# STM32_BOARD.net
KiCad netlist of a schematic drawn in Altium Designer
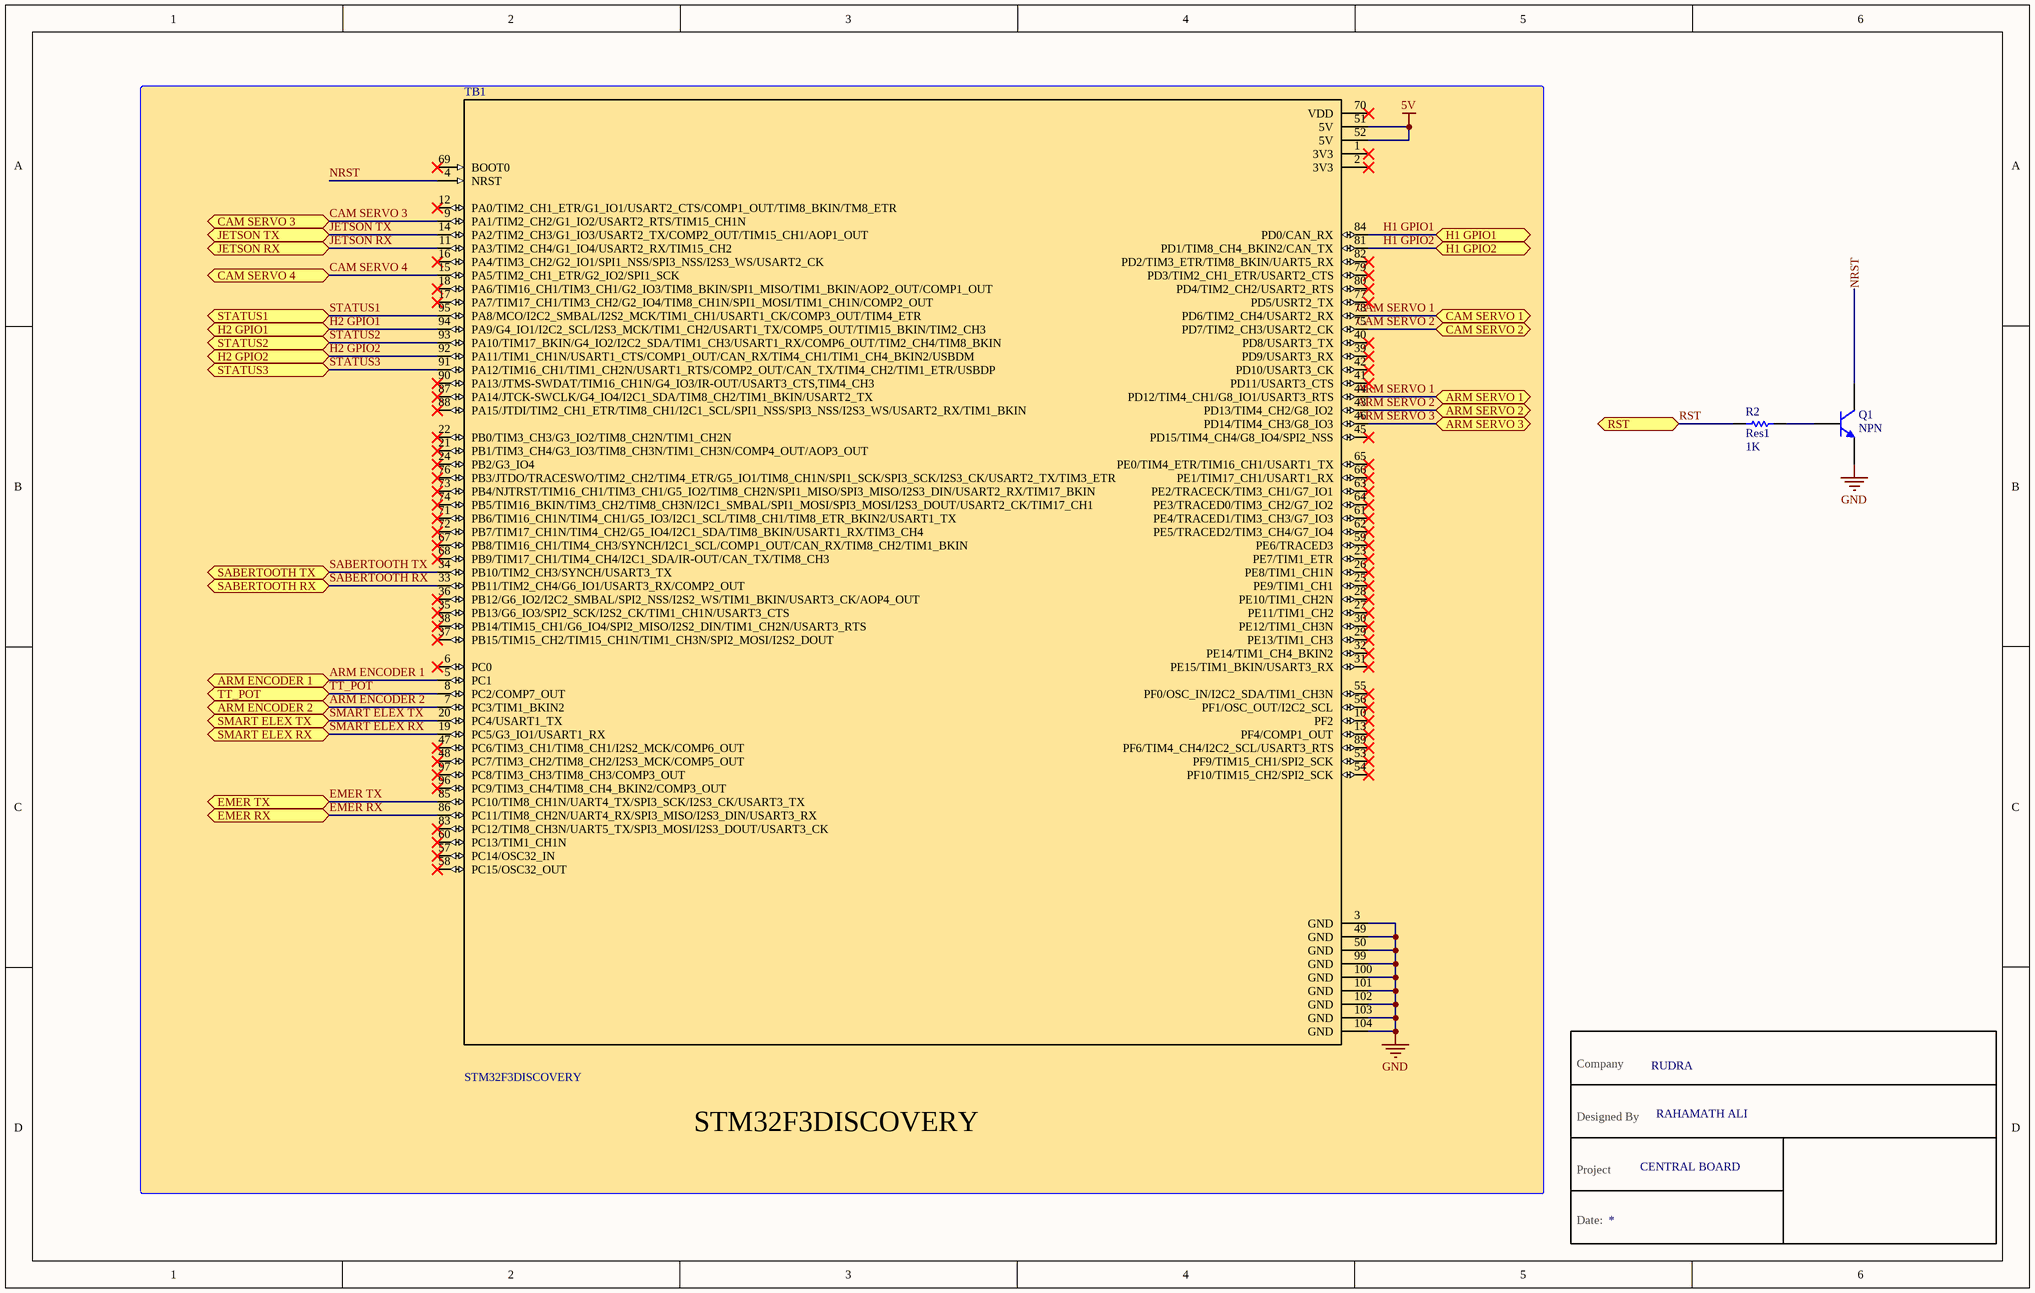
[diagram p0: STM32 BOARD.SchDoc]

(export (version "E")
  (design (tool "Eeschema 10.0.6"))
  (components
    (comp (ref "1")
      (value "Schematic Table")
      (fields
        (field (name "PROJECT") "CENTRAL BOARD")
        (field (name "DESIGNED BY") "RAHAMATH ALI")
        (field (name "COMPANY") "RUDRA")
      )
      (libsource (lib "schmatic") (part "Schematic Table"))
    )
    (comp (ref "Q1")
      (value "NPN")
      (footprint "TO-226-AA")
      (description "NPN Bipolar Transistor")
      (fields (field (name "PUBLISHER") "Altium Limited"))
      (libsource (lib "Miscellaneous Devices") (part "NPN"))
    )
    (comp (ref "R2")
      (value "Res1")
      (footprint "AXIAL-0.3")
      (description "Resistor")
      (fields (field (name "ALTIUM_VALUE") "1K") (field (name "PUBLISHER") "Altium Limited"))
      (libsource (lib "Miscellaneous Devices") (part "Res1"))
    )
    (comp (ref "TB1")
      (value "STM32F3DISCOVERY")
      (footprint "SHIELD_STM32F3DISCOVERY")
      (description "STM32F303VCT6 Discovery STM32F3 ARMÂ® CortexÂ®-M4 MCU 32-Bit Embedded Evaluation Board")
      (fields (field (name "MF") "STMicroelectronics"))
      (libsource (lib "CENTRAL BOARD LIBARAY") (part "STM32F3DISCOVERY"))
    )
  )
  (nets
    (net (code "1") (name "/ARM ENCODER 1") (class "Default")
      (node (ref "TB1") (pin "5") (pinfunction "PC1_5") (pintype "bidirectional"))
    )
    (net (code "2") (name "/ARM ENCODER 2") (class "Default")
      (node (ref "TB1") (pin "7") (pinfunction "PC3/TIM1_BKIN2_7") (pintype "bidirectional"))
    )
    (net (code "3") (name "/ARM SERVO 1") (class "Default")
      (node (ref "TB1") (pin "44") (pinfunction "PD12/TIM4_CH1/G8_IO1/USART3_RTS_44") (pintype "bidirectional"))
    )
    (net (code "4") (name "/ARM SERVO 2") (class "Default")
      (node (ref "TB1") (pin "43") (pinfunction "PD13/TIM4_CH2/G8_IO2_43") (pintype "bidirectional"))
    )
    (net (code "5") (name "/ARM SERVO 3") (class "Default")
      (node (ref "TB1") (pin "46") (pinfunction "PD14/TIM4_CH3/G8_IO3_46") (pintype "bidirectional"))
    )
    (net (code "6") (name "/CAM SERVO 1") (class "Default")
      (node (ref "TB1") (pin "78") (pinfunction "PD6/TIM2_CH4/USART2_RX_78") (pintype "bidirectional"))
    )
    (net (code "7") (name "/CAM SERVO 2") (class "Default")
      (node (ref "TB1") (pin "75") (pinfunction "PD7/TIM2_CH3/USART2_CK_75") (pintype "bidirectional"))
    )
    (net (code "8") (name "/CAM SERVO 3") (class "Default")
      (node (ref "TB1") (pin "9") (pinfunction "PA1/TIM2_CH2/G1_IO2/USART2_RTS/TIM15_CH1N_9") (pintype "bidirectional"))
    )
    (net (code "9") (name "/CAM SERVO 4") (class "Default")
      (node (ref "TB1") (pin "15") (pinfunction "PA5/TIM2_CH1_ETR/G2_IO2/SPI1_SCK_15") (pintype "bidirectional"))
    )
    (net (code "10") (name "/EMER RX") (class "Default")
      (node (ref "TB1") (pin "86") (pinfunction "PC11/TIM8_CH2N/UART4_RX/SPI3_MISO/I2S3_DIN/USART3_RX_86") (pintype "bidirectional"))
    )
    (net (code "11") (name "/EMER TX") (class "Default")
      (node (ref "TB1") (pin "85") (pinfunction "PC10/TIM8_CH1N/UART4_TX/SPI3_SCK/I2S3_CK/USART3_TX_85") (pintype "bidirectional"))
    )
    (net (code "12") (name "/H1 GPIO1") (class "Default")
      (node (ref "TB1") (pin "84") (pinfunction "PD0/CAN_RX_84") (pintype "bidirectional"))
    )
    (net (code "13") (name "/H1 GPIO2") (class "Default")
      (node (ref "TB1") (pin "81") (pinfunction "PD1/TIM8_CH4_BKIN2/CAN_TX_81") (pintype "bidirectional"))
    )
    (net (code "14") (name "/H2 GPIO1") (class "Default")
      (node (ref "TB1") (pin "94") (pinfunction "PA9/G4_IO1/I2C2_SCL/I2S3_MCK/TIM1_CH2/USART1_TX/COMP5_OUT/TIM15_BKIN/TIM2_CH3_94") (pintype "bidirectional"))
    )
    (net (code "15") (name "/H2 GPIO2") (class "Default")
      (node (ref "TB1") (pin "92") (pinfunction "PA11/TIM1_CH1N/USART1_CTS/COMP1_OUT/CAN_RX/TIM4_CH1/TIM1_CH4_BKIN2/USBDM_92") (pintype "bidirectional"))
    )
    (net (code "16") (name "/JETSON RX") (class "Default")
      (node (ref "TB1") (pin "11") (pinfunction "PA3/TIM2_CH4/G1_IO4/USART2_RX/TIM15_CH2_11") (pintype "bidirectional"))
    )
    (net (code "17") (name "/JETSON TX") (class "Default")
      (node (ref "TB1") (pin "14") (pinfunction "PA2/TIM2_CH3/G1_IO3/USART2_TX/COMP2_OUT/TIM15_CH1/AOP1_OUT_14") (pintype "bidirectional"))
    )
    (net (code "18") (name "/NRST") (class "Default")
      (node (ref "Q1") (pin "1") (pinfunction "C_1") (pintype "passive"))
      (node (ref "TB1") (pin "4") (pinfunction "NRST_4") (pintype "input"))
    )
    (net (code "19") (name "/RST") (class "Default")
      (node (ref "R2") (pin "1") (pinfunction "1_1") (pintype "passive"))
    )
    (net (code "20") (name "/SABERTOOTH RX") (class "Default")
      (node (ref "TB1") (pin "33") (pinfunction "PB11/TIM2_CH4/G6_IO1/USART3_RX/COMP2_OUT_33") (pintype "bidirectional"))
    )
    (net (code "21") (name "/SABERTOOTH TX") (class "Default")
      (node (ref "TB1") (pin "34") (pinfunction "PB10/TIM2_CH3/SYNCH/USART3_TX_34") (pintype "bidirectional"))
    )
    (net (code "22") (name "/SMART ELEX RX") (class "Default")
      (node (ref "TB1") (pin "19") (pinfunction "PC5/G3_IO1/USART1_RX_19") (pintype "bidirectional"))
    )
    (net (code "23") (name "/SMART ELEX TX") (class "Default")
      (node (ref "TB1") (pin "20") (pinfunction "PC4/USART1_TX_20") (pintype "bidirectional"))
    )
    (net (code "24") (name "/STATUS1") (class "Default")
      (node (ref "TB1") (pin "95") (pinfunction "PA8/MCO/I2C2_SMBAL/I2S2_MCK/TIM1_CH1/USART1_CK/COMP3_OUT/TIM4_ETR_95") (pintype "bidirectional"))
    )
    (net (code "25") (name "/STATUS2") (class "Default")
      (node (ref "TB1") (pin "93") (pinfunction "PA10/TIM17_BKIN/G4_IO2/I2C2_SDA/TIM1_CH3/USART1_RX/COMP6_OUT/TIM2_CH4/TIM8_BKIN_93") (pintype "bidirectional"))
    )
    (net (code "26") (name "/STATUS3") (class "Default")
      (node (ref "TB1") (pin "91") (pinfunction "PA12/TIM16_CH1/TIM1_CH2N/USART1_RTS/COMP2_OUT/CAN_TX/TIM4_CH2/TIM1_ETR/USBDP_91") (pintype "bidirectional"))
    )
    (net (code "27") (name "/TT_POT") (class "Default")
      (node (ref "TB1") (pin "8") (pinfunction "PC2/COMP7_OUT_8") (pintype "bidirectional"))
    )
    (net (code "28") (name "5V") (class "Default")
      (node (ref "TB1") (pin "51") (pinfunction "5V_51") (pintype "power_in"))
      (node (ref "TB1") (pin "52") (pinfunction "5V_52") (pintype "power_in"))
    )
    (net (code "29") (name "GND") (class "Default")
      (node (ref "Q1") (pin "3") (pinfunction "E_3") (pintype "passive"))
      (node (ref "TB1") (pin "100") (pinfunction "GND_100") (pintype "power_in"))
      (node (ref "TB1") (pin "101") (pinfunction "GND_101") (pintype "power_in"))
      (node (ref "TB1") (pin "102") (pinfunction "GND_102") (pintype "power_in"))
      (node (ref "TB1") (pin "103") (pinfunction "GND_103") (pintype "power_in"))
      (node (ref "TB1") (pin "104") (pinfunction "GND_104") (pintype "power_in"))
      (node (ref "TB1") (pin "3") (pinfunction "GND_3") (pintype "power_in"))
      (node (ref "TB1") (pin "49") (pinfunction "GND_49") (pintype "power_in"))
      (node (ref "TB1") (pin "50") (pinfunction "GND_50") (pintype "power_in"))
      (node (ref "TB1") (pin "99") (pinfunction "GND_99") (pintype "power_in"))
    )
    (net (code "30") (name "Net-(Q1-B)") (class "Default")
      (node (ref "Q1") (pin "2") (pinfunction "B_2") (pintype "passive"))
      (node (ref "R2") (pin "2") (pinfunction "2_2") (pintype "passive"))
    )
    (net (code "31") (name "unconnected-(TB1-3V3-Pad1)") (class "Default")
      (node (ref "TB1") (pin "1") (pinfunction "3V3_1") (pintype "power_in+no_connect"))
    )
    (net (code "32") (name "unconnected-(TB1-3V3-Pad2)") (class "Default")
      (node (ref "TB1") (pin "2") (pinfunction "3V3_2") (pintype "power_in+no_connect"))
    )
    (net (code "33") (name "unconnected-(TB1-BOOT0-Pad69)") (class "Default")
      (node (ref "TB1") (pin "69") (pinfunction "BOOT0_69") (pintype "input+no_connect"))
    )
    (net (code "34") (name "unconnected-(TB1-PA0{slash}TIM2_CH1_ETR{slash}G1_IO1{slash}USART2_CTS{slash}COMP1_OUT{slash}TIM8_BKIN{slash}TM8_ETR-Pad12)") (class "Default")
      (node (ref "TB1") (pin "12") (pinfunction "PA0/TIM2_CH1_ETR/G1_IO1/USART2_CTS/COMP1_OUT/TIM8_BKIN/TM8_ETR_12") (pintype "bidirectional+no_connect"))
    )
    (net (code "35") (name "unconnected-(TB1-PA4{slash}TIM3_CH2{slash}G2_IO1{slash}SPI1_NSS{slash}SPI3_NSS{slash}I2S3_WS{slash}USART2_CK-Pad16)") (class "Default")
      (node (ref "TB1") (pin "16") (pinfunction "PA4/TIM3_CH2/G2_IO1/SPI1_NSS/SPI3_NSS/I2S3_WS/USART2_CK_16") (pintype "bidirectional+no_connect"))
    )
    (net (code "36") (name "unconnected-(TB1-PA6{slash}TIM16_CH1{slash}TIM3_CH1{slash}G2_IO3{slash}TIM8_BKIN{slash}SPI1_MISO{slash}TIM1_BKIN{slash}AOP2_OUT{slash}COMP1_OUT-Pad18)") (class "Default")
      (node (ref "TB1") (pin "18") (pinfunction "PA6/TIM16_CH1/TIM3_CH1/G2_IO3/TIM8_BKIN/SPI1_MISO/TIM1_BKIN/AOP2_OUT/COMP1_OUT_18") (pintype "bidirectional+no_connect"))
    )
    (net (code "37") (name "unconnected-(TB1-PA7{slash}TIM17_CH1{slash}TIM3_CH2{slash}G2_IO4{slash}TIM8_CH1N{slash}SPI1_MOSI{slash}TIM1_CH1N{slash}COMP2_OUT-Pad17)") (class "Default")
      (node (ref "TB1") (pin "17") (pinfunction "PA7/TIM17_CH1/TIM3_CH2/G2_IO4/TIM8_CH1N/SPI1_MOSI/TIM1_CH1N/COMP2_OUT_17") (pintype "bidirectional+no_connect"))
    )
    (net (code "38") (name "unconnected-(TB1-PA13{slash}JTMS-SWDAT{slash}TIM16_CH1N{slash}G4_IO3{slash}IR-OUT{slash}USART3_CTS,TIM4_CH3-Pad90)") (class "Default")
      (node (ref "TB1") (pin "90") (pinfunction "PA13/JTMS-SWDAT/TIM16_CH1N/G4_IO3/IR-OUT/USART3_CTS,TIM4_CH3_90") (pintype "bidirectional+no_connect"))
    )
    (net (code "39") (name "unconnected-(TB1-PA14{slash}JTCK-SWCLK{slash}G4_IO4{slash}I2C1_SDA{slash}TIM8_CH2{slash}TIM1_BKIN{slash}USART2_TX-Pad87)") (class "Default")
      (node (ref "TB1") (pin "87") (pinfunction "PA14/JTCK-SWCLK/G4_IO4/I2C1_SDA/TIM8_CH2/TIM1_BKIN/USART2_TX_87") (pintype "bidirectional+no_connect"))
    )
    (net (code "40") (name "unconnected-(TB1-PA15{slash}JTDI{slash}TIM2_CH1_ETR{slash}TIM8_CH1{slash}I2C1_SCL{slash}SPI1_NSS{slash}SPI3_NSS{slash}I2S3_WS{slash}USART2_RX{slash}TIM1_BKIN-Pad88)") (class "Default")
      (node (ref "TB1") (pin "88") (pinfunction "PA15/JTDI/TIM2_CH1_ETR/TIM8_CH1/I2C1_SCL/SPI1_NSS/SPI3_NSS/I2S3_WS/USART2_RX/TIM1_BKIN_88") (pintype "bidirectional+no_connect"))
    )
    (net (code "41") (name "unconnected-(TB1-PB0{slash}TIM3_CH3{slash}G3_IO2{slash}TIM8_CH2N{slash}TIM1_CH2N-Pad22)") (class "Default")
      (node (ref "TB1") (pin "22") (pinfunction "PB0/TIM3_CH3/G3_IO2/TIM8_CH2N/TIM1_CH2N_22") (pintype "bidirectional+no_connect"))
    )
    (net (code "42") (name "unconnected-(TB1-PB1{slash}TIM3_CH4{slash}G3_IO3{slash}TIM8_CH3N{slash}TIM1_CH3N{slash}COMP4_OUT{slash}AOP3_OUT-Pad21)") (class "Default")
      (node (ref "TB1") (pin "21") (pinfunction "PB1/TIM3_CH4/G3_IO3/TIM8_CH3N/TIM1_CH3N/COMP4_OUT/AOP3_OUT_21") (pintype "bidirectional+no_connect"))
    )
    (net (code "43") (name "unconnected-(TB1-PB2{slash}G3_IO4-Pad24)") (class "Default")
      (node (ref "TB1") (pin "24") (pinfunction "PB2/G3_IO4_24") (pintype "bidirectional+no_connect"))
    )
    (net (code "44") (name "unconnected-(TB1-PB3{slash}JTDO{slash}TRACESWO{slash}TIM2_CH2{slash}TIM4_ETR{slash}G5_IO1{slash}TIM8_CH1N{slash}SPI1_SCK{slash}SPI3_SCK{slash}I2S3_CK{slash}USART2_TX{slash}TIM3_ETR-Pad76)") (class "Default")
      (node (ref "TB1") (pin "76") (pinfunction "PB3/JTDO/TRACESWO/TIM2_CH2/TIM4_ETR/G5_IO1/TIM8_CH1N/SPI1_SCK/SPI3_SCK/I2S3_CK/USART2_TX/TIM3_ETR_76") (pintype "bidirectional+no_connect"))
    )
    (net (code "45") (name "unconnected-(TB1-PB4{slash}NJTRST{slash}TIM16_CH1{slash}TIM3_CH1{slash}G5_IO2{slash}TIM8_CH2N{slash}SPI1_MISO{slash}SPI3_MISO{slash}I2S3_DIN{slash}USART2_RX{slash}TIM17_BKIN-Pad73)") (class "Default")
      (node (ref "TB1") (pin "73") (pinfunction "PB4/NJTRST/TIM16_CH1/TIM3_CH1/G5_IO2/TIM8_CH2N/SPI1_MISO/SPI3_MISO/I2S3_DIN/USART2_RX/TIM17_BKIN_73") (pintype "bidirectional+no_connect"))
    )
    (net (code "46") (name "unconnected-(TB1-PB5{slash}TIM16_BKIN{slash}TIM3_CH2{slash}TIM8_CH3N{slash}I2C1_SMBAL{slash}SPI1_MOSI{slash}SPI3_MOSI{slash}I2S3_DOUT{slash}USART2_CK{slash}TIM17_CH1-Pad74)") (class "Default")
      (node (ref "TB1") (pin "74") (pinfunction "PB5/TIM16_BKIN/TIM3_CH2/TIM8_CH3N/I2C1_SMBAL/SPI1_MOSI/SPI3_MOSI/I2S3_DOUT/USART2_CK/TIM17_CH1_74") (pintype "bidirectional+no_connect"))
    )
    (net (code "47") (name "unconnected-(TB1-PB6{slash}TIM16_CH1N{slash}TIM4_CH1{slash}G5_IO3{slash}I2C1_SCL{slash}TIM8_CH1{slash}TIM8_ETR_BKIN2{slash}USART1_TX-Pad71)") (class "Default")
      (node (ref "TB1") (pin "71") (pinfunction "PB6/TIM16_CH1N/TIM4_CH1/G5_IO3/I2C1_SCL/TIM8_CH1/TIM8_ETR_BKIN2/USART1_TX_71") (pintype "bidirectional+no_connect"))
    )
    (net (code "48") (name "unconnected-(TB1-PB7{slash}TIM17_CH1N{slash}TIM4_CH2{slash}G5_IO4{slash}I2C1_SDA{slash}TIM8_BKIN{slash}USART1_RX{slash}TIM3_CH4-Pad72)") (class "Default")
      (node (ref "TB1") (pin "72") (pinfunction "PB7/TIM17_CH1N/TIM4_CH2/G5_IO4/I2C1_SDA/TIM8_BKIN/USART1_RX/TIM3_CH4_72") (pintype "bidirectional+no_connect"))
    )
    (net (code "49") (name "unconnected-(TB1-PB8{slash}TIM16_CH1{slash}TIM4_CH3{slash}SYNCH{slash}I2C1_SCL{slash}COMP1_OUT{slash}CAN_RX{slash}TIM8_CH2{slash}TIM1_BKIN-Pad67)") (class "Default")
      (node (ref "TB1") (pin "67") (pinfunction "PB8/TIM16_CH1/TIM4_CH3/SYNCH/I2C1_SCL/COMP1_OUT/CAN_RX/TIM8_CH2/TIM1_BKIN_67") (pintype "bidirectional+no_connect"))
    )
    (net (code "50") (name "unconnected-(TB1-PB9{slash}TIM17_CH1{slash}TIM4_CH4{slash}I2C1_SDA{slash}IR-OUT{slash}CAN_TX{slash}TIM8_CH3-Pad68)") (class "Default")
      (node (ref "TB1") (pin "68") (pinfunction "PB9/TIM17_CH1/TIM4_CH4/I2C1_SDA/IR-OUT/CAN_TX/TIM8_CH3_68") (pintype "bidirectional+no_connect"))
    )
    (net (code "51") (name "unconnected-(TB1-PB12{slash}G6_IO2{slash}I2C2_SMBAL{slash}SPI2_NSS{slash}I2S2_WS{slash}TIM1_BKIN{slash}USART3_CK{slash}AOP4_OUT-Pad36)") (class "Default")
      (node (ref "TB1") (pin "36") (pinfunction "PB12/G6_IO2/I2C2_SMBAL/SPI2_NSS/I2S2_WS/TIM1_BKIN/USART3_CK/AOP4_OUT_36") (pintype "bidirectional+no_connect"))
    )
    (net (code "52") (name "unconnected-(TB1-PB13{slash}G6_IO3{slash}SPI2_SCK{slash}I2S2_CK{slash}TIM1_CH1N{slash}USART3_CTS-Pad35)") (class "Default")
      (node (ref "TB1") (pin "35") (pinfunction "PB13/G6_IO3/SPI2_SCK/I2S2_CK/TIM1_CH1N/USART3_CTS_35") (pintype "bidirectional+no_connect"))
    )
    (net (code "53") (name "unconnected-(TB1-PB14{slash}TIM15_CH1{slash}G6_IO4{slash}SPI2_MISO{slash}I2S2_DIN{slash}TIM1_CH2N{slash}USART3_RTS-Pad38)") (class "Default")
      (node (ref "TB1") (pin "38") (pinfunction "PB14/TIM15_CH1/G6_IO4/SPI2_MISO/I2S2_DIN/TIM1_CH2N/USART3_RTS_38") (pintype "bidirectional+no_connect"))
    )
    (net (code "54") (name "unconnected-(TB1-PB15{slash}TIM15_CH2{slash}TIM15_CH1N{slash}TIM1_CH3N{slash}SPI2_MOSI{slash}I2S2_DOUT-Pad37)") (class "Default")
      (node (ref "TB1") (pin "37") (pinfunction "PB15/TIM15_CH2/TIM15_CH1N/TIM1_CH3N/SPI2_MOSI/I2S2_DOUT_37") (pintype "bidirectional+no_connect"))
    )
    (net (code "55") (name "unconnected-(TB1-PC0-Pad6)") (class "Default")
      (node (ref "TB1") (pin "6") (pinfunction "PC0_6") (pintype "bidirectional+no_connect"))
    )
    (net (code "56") (name "unconnected-(TB1-PC6{slash}TIM3_CH1{slash}TIM8_CH1{slash}I2S2_MCK{slash}COMP6_OUT-Pad47)") (class "Default")
      (node (ref "TB1") (pin "47") (pinfunction "PC6/TIM3_CH1/TIM8_CH1/I2S2_MCK/COMP6_OUT_47") (pintype "bidirectional+no_connect"))
    )
    (net (code "57") (name "unconnected-(TB1-PC7{slash}TIM3_CH2{slash}TIM8_CH2{slash}I2S3_MCK{slash}COMP5_OUT-Pad48)") (class "Default")
      (node (ref "TB1") (pin "48") (pinfunction "PC7/TIM3_CH2/TIM8_CH2/I2S3_MCK/COMP5_OUT_48") (pintype "bidirectional+no_connect"))
    )
    (net (code "58") (name "unconnected-(TB1-PC8{slash}TIM3_CH3{slash}TIM8_CH3{slash}COMP3_OUT-Pad97)") (class "Default")
      (node (ref "TB1") (pin "97") (pinfunction "PC8/TIM3_CH3/TIM8_CH3/COMP3_OUT_97") (pintype "bidirectional+no_connect"))
    )
    (net (code "59") (name "unconnected-(TB1-PC9{slash}TIM3_CH4{slash}TIM8_CH4_BKIN2{slash}COMP3_OUT-Pad96)") (class "Default")
      (node (ref "TB1") (pin "96") (pinfunction "PC9/TIM3_CH4/TIM8_CH4_BKIN2/COMP3_OUT_96") (pintype "bidirectional+no_connect"))
    )
    (net (code "60") (name "unconnected-(TB1-PC12{slash}TIM8_CH3N{slash}UART5_TX{slash}SPI3_MOSI{slash}I2S3_DOUT{slash}USART3_CK-Pad83)") (class "Default")
      (node (ref "TB1") (pin "83") (pinfunction "PC12/TIM8_CH3N/UART5_TX/SPI3_MOSI/I2S3_DOUT/USART3_CK_83") (pintype "bidirectional+no_connect"))
    )
    (net (code "61") (name "unconnected-(TB1-PC13{slash}TIM1_CH1N-Pad60)") (class "Default")
      (node (ref "TB1") (pin "60") (pinfunction "PC13/TIM1_CH1N_60") (pintype "bidirectional+no_connect"))
    )
    (net (code "62") (name "unconnected-(TB1-PC14{slash}OSC32_IN-Pad57)") (class "Default")
      (node (ref "TB1") (pin "57") (pinfunction "PC14/OSC32_IN_57") (pintype "bidirectional+no_connect"))
    )
    (net (code "63") (name "unconnected-(TB1-PC15{slash}OSC32_OUT-Pad58)") (class "Default")
      (node (ref "TB1") (pin "58") (pinfunction "PC15/OSC32_OUT_58") (pintype "bidirectional+no_connect"))
    )
    (net (code "64") (name "unconnected-(TB1-PD2{slash}TIM3_ETR{slash}TIM8_BKIN{slash}UART5_RX-Pad82)") (class "Default")
      (node (ref "TB1") (pin "82") (pinfunction "PD2/TIM3_ETR/TIM8_BKIN/UART5_RX_82") (pintype "bidirectional+no_connect"))
    )
    (net (code "65") (name "unconnected-(TB1-PD3{slash}TIM2_CH1_ETR{slash}USART2_CTS-Pad79)") (class "Default")
      (node (ref "TB1") (pin "79") (pinfunction "PD3/TIM2_CH1_ETR/USART2_CTS_79") (pintype "bidirectional+no_connect"))
    )
    (net (code "66") (name "unconnected-(TB1-PD4{slash}TIM2_CH2{slash}USART2_RTS-Pad80)") (class "Default")
      (node (ref "TB1") (pin "80") (pinfunction "PD4/TIM2_CH2/USART2_RTS_80") (pintype "bidirectional+no_connect"))
    )
    (net (code "67") (name "unconnected-(TB1-PD5{slash}USRT2_TX-Pad77)") (class "Default")
      (node (ref "TB1") (pin "77") (pinfunction "PD5/USRT2_TX_77") (pintype "bidirectional+no_connect"))
    )
    (net (code "68") (name "unconnected-(TB1-PD8{slash}USART3_TX-Pad40)") (class "Default")
      (node (ref "TB1") (pin "40") (pinfunction "PD8/USART3_TX_40") (pintype "bidirectional+no_connect"))
    )
    (net (code "69") (name "unconnected-(TB1-PD9{slash}USART3_RX-Pad39)") (class "Default")
      (node (ref "TB1") (pin "39") (pinfunction "PD9/USART3_RX_39") (pintype "bidirectional+no_connect"))
    )
    (net (code "70") (name "unconnected-(TB1-PD10{slash}USART3_CK-Pad42)") (class "Default")
      (node (ref "TB1") (pin "42") (pinfunction "PD10/USART3_CK_42") (pintype "bidirectional+no_connect"))
    )
    (net (code "71") (name "unconnected-(TB1-PD11{slash}USART3_CTS-Pad41)") (class "Default")
      (node (ref "TB1") (pin "41") (pinfunction "PD11/USART3_CTS_41") (pintype "bidirectional+no_connect"))
    )
    (net (code "72") (name "unconnected-(TB1-PD15{slash}TIM4_CH4{slash}G8_IO4{slash}SPI2_NSS-Pad45)") (class "Default")
      (node (ref "TB1") (pin "45") (pinfunction "PD15/TIM4_CH4/G8_IO4/SPI2_NSS_45") (pintype "bidirectional+no_connect"))
    )
    (net (code "73") (name "unconnected-(TB1-PE0{slash}TIM4_ETR{slash}TIM16_CH1{slash}USART1_TX-Pad65)") (class "Default")
      (node (ref "TB1") (pin "65") (pinfunction "PE0/TIM4_ETR/TIM16_CH1/USART1_TX_65") (pintype "bidirectional+no_connect"))
    )
    (net (code "74") (name "unconnected-(TB1-PE1{slash}TIM17_CH1{slash}USART1_RX-Pad66)") (class "Default")
      (node (ref "TB1") (pin "66") (pinfunction "PE1/TIM17_CH1/USART1_RX_66") (pintype "bidirectional+no_connect"))
    )
    (net (code "75") (name "unconnected-(TB1-PE2{slash}TRACECK{slash}TIM3_CH1{slash}G7_IO1-Pad63)") (class "Default")
      (node (ref "TB1") (pin "63") (pinfunction "PE2/TRACECK/TIM3_CH1/G7_IO1_63") (pintype "bidirectional+no_connect"))
    )
    (net (code "76") (name "unconnected-(TB1-PE3{slash}TRACED0{slash}TIM3_CH2{slash}G7_IO2-Pad64)") (class "Default")
      (node (ref "TB1") (pin "64") (pinfunction "PE3/TRACED0/TIM3_CH2/G7_IO2_64") (pintype "bidirectional+no_connect"))
    )
    (net (code "77") (name "unconnected-(TB1-PE4{slash}TRACED1{slash}TIM3_CH3{slash}G7_IO3-Pad61)") (class "Default")
      (node (ref "TB1") (pin "61") (pinfunction "PE4/TRACED1/TIM3_CH3/G7_IO3_61") (pintype "bidirectional+no_connect"))
    )
    (net (code "78") (name "unconnected-(TB1-PE5{slash}TRACED2{slash}TIM3_CH4{slash}G7_IO4-Pad62)") (class "Default")
      (node (ref "TB1") (pin "62") (pinfunction "PE5/TRACED2/TIM3_CH4/G7_IO4_62") (pintype "bidirectional+no_connect"))
    )
    (net (code "79") (name "unconnected-(TB1-PE6{slash}TRACED3-Pad59)") (class "Default")
      (node (ref "TB1") (pin "59") (pinfunction "PE6/TRACED3_59") (pintype "bidirectional+no_connect"))
    )
    (net (code "80") (name "unconnected-(TB1-PE7{slash}TIM1_ETR-Pad23)") (class "Default")
      (node (ref "TB1") (pin "23") (pinfunction "PE7/TIM1_ETR_23") (pintype "bidirectional+no_connect"))
    )
    (net (code "81") (name "unconnected-(TB1-PE8{slash}TIM1_CH1N-Pad26)") (class "Default")
      (node (ref "TB1") (pin "26") (pinfunction "PE8/TIM1_CH1N_26") (pintype "bidirectional+no_connect"))
    )
    (net (code "82") (name "unconnected-(TB1-PE9{slash}TIM1_CH1-Pad25)") (class "Default")
      (node (ref "TB1") (pin "25") (pinfunction "PE9/TIM1_CH1_25") (pintype "bidirectional+no_connect"))
    )
    (net (code "83") (name "unconnected-(TB1-PE10{slash}TIM1_CH2N-Pad28)") (class "Default")
      (node (ref "TB1") (pin "28") (pinfunction "PE10/TIM1_CH2N_28") (pintype "bidirectional+no_connect"))
    )
    (net (code "84") (name "unconnected-(TB1-PE11{slash}TIM1_CH2-Pad27)") (class "Default")
      (node (ref "TB1") (pin "27") (pinfunction "PE11/TIM1_CH2_27") (pintype "bidirectional+no_connect"))
    )
    (net (code "85") (name "unconnected-(TB1-PE12{slash}TIM1_CH3N-Pad30)") (class "Default")
      (node (ref "TB1") (pin "30") (pinfunction "PE12/TIM1_CH3N_30") (pintype "bidirectional+no_connect"))
    )
    (net (code "86") (name "unconnected-(TB1-PE13{slash}TIM1_CH3-Pad29)") (class "Default")
      (node (ref "TB1") (pin "29") (pinfunction "PE13/TIM1_CH3_29") (pintype "bidirectional+no_connect"))
    )
    (net (code "87") (name "unconnected-(TB1-PE14{slash}TIM1_CH4_BKIN2-Pad32)") (class "Default")
      (node (ref "TB1") (pin "32") (pinfunction "PE14/TIM1_CH4_BKIN2_32") (pintype "bidirectional+no_connect"))
    )
    (net (code "88") (name "unconnected-(TB1-PE15{slash}TIM1_BKIN{slash}USART3_RX-Pad31)") (class "Default")
      (node (ref "TB1") (pin "31") (pinfunction "PE15/TIM1_BKIN/USART3_RX_31") (pintype "bidirectional+no_connect"))
    )
    (net (code "89") (name "unconnected-(TB1-PF0{slash}OSC_IN{slash}I2C2_SDA{slash}TIM1_CH3N-Pad55)") (class "Default")
      (node (ref "TB1") (pin "55") (pinfunction "PF0/OSC_IN/I2C2_SDA/TIM1_CH3N_55") (pintype "bidirectional+no_connect"))
    )
    (net (code "90") (name "unconnected-(TB1-PF1{slash}OSC_OUT{slash}I2C2_SCL-Pad56)") (class "Default")
      (node (ref "TB1") (pin "56") (pinfunction "PF1/OSC_OUT/I2C2_SCL_56") (pintype "bidirectional+no_connect"))
    )
    (net (code "91") (name "unconnected-(TB1-PF2-Pad10)") (class "Default")
      (node (ref "TB1") (pin "10") (pinfunction "PF2_10") (pintype "bidirectional+no_connect"))
    )
    (net (code "92") (name "unconnected-(TB1-PF4{slash}COMP1_OUT-Pad13)") (class "Default")
      (node (ref "TB1") (pin "13") (pinfunction "PF4/COMP1_OUT_13") (pintype "bidirectional+no_connect"))
    )
    (net (code "93") (name "unconnected-(TB1-PF6{slash}TIM4_CH4{slash}I2C2_SCL{slash}USART3_RTS-Pad89)") (class "Default")
      (node (ref "TB1") (pin "89") (pinfunction "PF6/TIM4_CH4/I2C2_SCL/USART3_RTS_89") (pintype "bidirectional+no_connect"))
    )
    (net (code "94") (name "unconnected-(TB1-PF9{slash}TIM15_CH1{slash}SPI2_SCK-Pad53)") (class "Default")
      (node (ref "TB1") (pin "53") (pinfunction "PF9/TIM15_CH1/SPI2_SCK_53") (pintype "bidirectional+no_connect"))
    )
    (net (code "95") (name "unconnected-(TB1-PF10{slash}TIM15_CH2{slash}SPI2_SCK-Pad54)") (class "Default")
      (node (ref "TB1") (pin "54") (pinfunction "PF10/TIM15_CH2/SPI2_SCK_54") (pintype "bidirectional+no_connect"))
    )
    (net (code "96") (name "unconnected-(TB1-VDD-Pad70)") (class "Default")
      (node (ref "TB1") (pin "70") (pinfunction "VDD_70") (pintype "power_in+no_connect"))
    )
  )
)
